# UKU207xx_power_board.net
KiCad netlist of a schematic drawn in Altium Designer
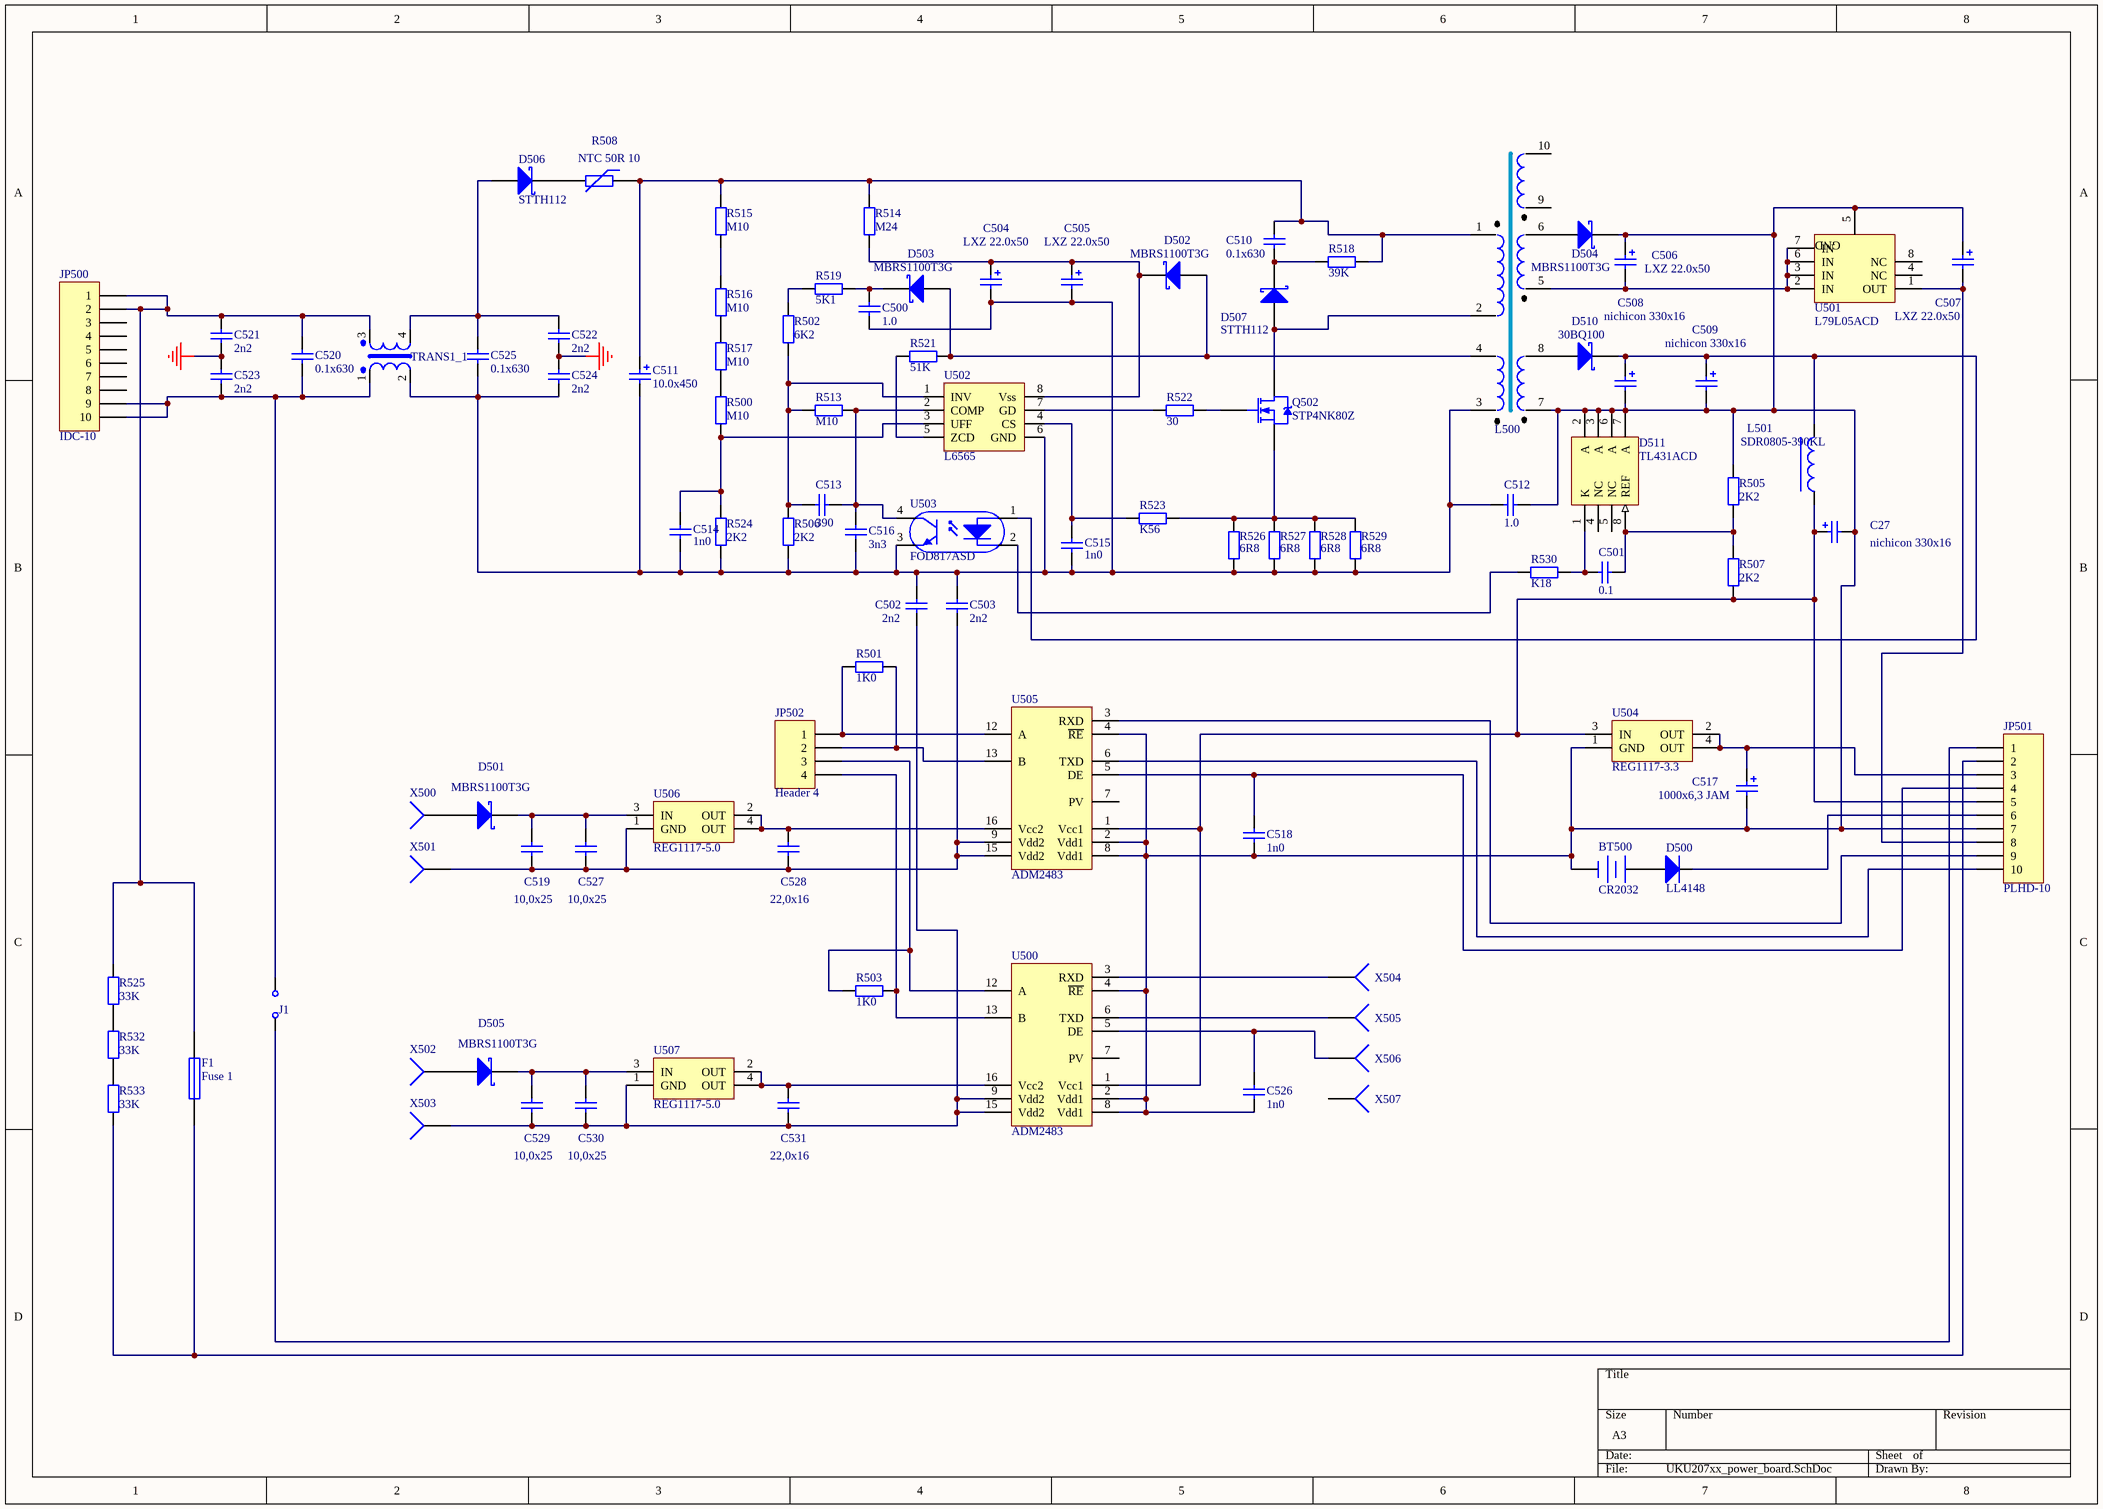
[diagram p0: UKU207xx_power_board.SchDoc]

(export (version "E")
  (design (tool "Eeschema 10.0.6"))
  (components
    (comp (ref "BT500")
      (value "CR2032")
      (footprint "BAT_HOLD_SMD1")
      (description "Multicell Battery")
      (fields (field (name "MANUFACTURER") "Generic Components") (field (name "PUBLISHER") "Altium Limited"))
      (libsource (lib "Miscellaneous Devices") (part "Battery"))
    )
    (comp (ref "C27")
      (value "nichicon 330x16")
      (footprint "el3")
      (description "Polarized Capacitor (Radial)")
      (fields (field (name "MANUFACTURER") "Generic Components") (field (name "PUBLISHER") "Altium Limited"))
      (libsource (lib "PAL") (part "Cap Pol1"))
    )
    (comp (ref "C500")
      (value "1.0")
      (footprint "_1206")
      (description "Capacitor (Semiconductor SIM Model)")
      (fields (field (name "MANUFACTURER") "Generic Components") (field (name "PUBLISHER") "Altium Limited"))
      (libsource (lib "Miscellaneous Devices") (part "Cap Semi"))
    )
    (comp (ref "C501")
      (value "0.1")
      (footprint "_1206")
      (description "Capacitor (Semiconductor SIM Model)")
      (fields (field (name "MANUFACTURER") "Generic Components") (field (name "PUBLISHER") "Altium Limited"))
      (libsource (lib "Miscellaneous Devices") (part "Cap Semi"))
    )
    (comp (ref "C502")
      (value "2n2")
      (footprint "C8")
      (description "Capacitor (Semiconductor SIM Model)")
      (fields (field (name "MANUFACTURER") "Generic Components") (field (name "PUBLISHER") "Altium Limited"))
      (libsource (lib "Miscellaneous Devices") (part "Cap Semi"))
    )
    (comp (ref "C503")
      (value "2n2")
      (footprint "C8")
      (description "Capacitor (Semiconductor SIM Model)")
      (fields (field (name "MANUFACTURER") "Generic Components") (field (name "PUBLISHER") "Altium Limited"))
      (libsource (lib "Miscellaneous Devices") (part "Cap Semi"))
    )
    (comp (ref "C504")
      (value "LXZ 22.0x50")
      (footprint "el3")
      (description "Polarized Capacitor (Radial)")
      (fields (field (name "MANUFACTURER") "Generic Components") (field (name "PUBLISHER") "Altium Limited"))
      (libsource (lib "PAL") (part "Cap Pol1"))
    )
    (comp (ref "C505")
      (value "LXZ 22.0x50")
      (footprint "el3")
      (description "Polarized Capacitor (Radial)")
      (fields (field (name "MANUFACTURER") "Generic Components") (field (name "PUBLISHER") "Altium Limited"))
      (libsource (lib "PAL") (part "Cap Pol1"))
    )
    (comp (ref "C506")
      (value "LXZ 22.0x50")
      (footprint "el3")
      (description "Polarized Capacitor (Radial)")
      (fields (field (name "MANUFACTURER") "Generic Components") (field (name "PUBLISHER") "Altium Limited"))
      (libsource (lib "PAL") (part "Cap Pol1"))
    )
    (comp (ref "C507")
      (value "LXZ 22.0x50")
      (footprint "el3")
      (description "Polarized Capacitor (Radial)")
      (fields (field (name "MANUFACTURER") "Generic Components") (field (name "PUBLISHER") "Altium Limited"))
      (libsource (lib "PAL") (part "Cap Pol1"))
    )
    (comp (ref "C508")
      (value "nichicon 330x16")
      (footprint "el3")
      (description "Polarized Capacitor (Radial)")
      (fields (field (name "MANUFACTURER") "Generic Components") (field (name "PUBLISHER") "Altium Limited"))
      (libsource (lib "PAL") (part "Cap Pol1"))
    )
    (comp (ref "C509")
      (value "nichicon 330x16")
      (footprint "el3")
      (description "Polarized Capacitor (Radial)")
      (fields (field (name "MANUFACTURER") "Generic Components") (field (name "PUBLISHER") "Altium Limited"))
      (libsource (lib "PAL") (part "Cap Pol1"))
    )
    (comp (ref "C510")
      (value "0.1x630")
      (footprint "c15")
      (description "Capacitor (Semiconductor SIM Model)")
      (fields (field (name "MANUFACTURER") "Generic Components") (field (name "PUBLISHER") "Altium Limited"))
      (libsource (lib "Miscellaneous Devices") (part "Cap Semi"))
    )
    (comp (ref "C511")
      (value "10.0x450")
      (footprint "el_15_25_h")
      (description "Polarized Capacitor (Radial)")
      (fields (field (name "MANUFACTURER") "Generic Components") (field (name "PUBLISHER") "Altium Limited"))
      (libsource (lib "PAL") (part "Cap Pol1"))
    )
    (comp (ref "C512")
      (value "1.0")
      (footprint "C8")
      (description "Capacitor (Semiconductor SIM Model)")
      (fields (field (name "MANUFACTURER") "Generic Components") (field (name "PUBLISHER") "Altium Limited"))
      (libsource (lib "Miscellaneous Devices") (part "Cap Semi"))
    )
    (comp (ref "C513")
      (value "390")
      (footprint "_1206")
      (description "Capacitor (Semiconductor SIM Model)")
      (fields (field (name "MANUFACTURER") "Generic Components") (field (name "PUBLISHER") "Altium Limited"))
      (libsource (lib "Miscellaneous Devices") (part "Cap Semi"))
    )
    (comp (ref "C514")
      (value "1n0")
      (footprint "_1206")
      (description "Capacitor (Semiconductor SIM Model)")
      (fields (field (name "MANUFACTURER") "Generic Components") (field (name "PUBLISHER") "Altium Limited"))
      (libsource (lib "Miscellaneous Devices") (part "Cap Semi"))
    )
    (comp (ref "C515")
      (value "1n0")
      (footprint "_1206")
      (description "Capacitor (Semiconductor SIM Model)")
      (fields (field (name "MANUFACTURER") "Generic Components") (field (name "PUBLISHER") "Altium Limited"))
      (libsource (lib "Miscellaneous Devices") (part "Cap Semi"))
    )
    (comp (ref "C516")
      (value "3n3")
      (footprint "_1206")
      (description "Capacitor (Semiconductor SIM Model)")
      (fields (field (name "MANUFACTURER") "Generic Components") (field (name "PUBLISHER") "Altium Limited"))
      (libsource (lib "Miscellaneous Devices") (part "Cap Semi"))
    )
    (comp (ref "C517")
      (value "1000x6,3 JAM")
      (footprint "el5")
      (description "Polarized Capacitor (Radial)")
      (fields (field (name "MANUFACTURER") "Generic Components") (field (name "PUBLISHER") "Altium Limited"))
      (libsource (lib "PAL") (part "Cap Pol1"))
    )
    (comp (ref "C518")
      (value "1n0")
      (footprint "_1206")
      (description "Capacitor (Semiconductor SIM Model)")
      (fields (field (name "MANUFACTURER") "Generic Components") (field (name "PUBLISHER") "Altium Limited"))
      (libsource (lib "Miscellaneous Devices") (part "Cap Semi"))
    )
    (comp (ref "C519")
      (value "1.0")
      (footprint "_1206")
      (description "Capacitor (Semiconductor SIM Model)")
      (fields
        (field (name "MANUFACTURER") "Generic Components")
        (field (name "ALTIUM_VALUE") "10,0x25")
        (field (name "PUBLISHER") "Altium Limited")
      )
      (libsource (lib "Miscellaneous Devices") (part "Cap Semi"))
    )
    (comp (ref "C520")
      (value "0.1x630")
      (footprint "c15")
      (description "Capacitor (Semiconductor SIM Model)")
      (fields (field (name "MANUFACTURER") "Generic Components") (field (name "PUBLISHER") "Altium Limited"))
      (libsource (lib "Miscellaneous Devices") (part "Cap Semi"))
    )
    (comp (ref "C521")
      (value "2n2")
      (footprint "C8")
      (description "Capacitor (Semiconductor SIM Model)")
      (fields (field (name "MANUFACTURER") "Generic Components") (field (name "PUBLISHER") "Altium Limited"))
      (libsource (lib "Miscellaneous Devices") (part "Cap Semi"))
    )
    (comp (ref "C522")
      (value "2n2")
      (footprint "c8")
      (description "Capacitor (Semiconductor SIM Model)")
      (fields (field (name "MANUFACTURER") "Generic Components") (field (name "PUBLISHER") "Altium Limited"))
      (libsource (lib "Miscellaneous Devices") (part "Cap Semi"))
    )
    (comp (ref "C523")
      (value "2n2")
      (footprint "c8")
      (description "Capacitor (Semiconductor SIM Model)")
      (fields (field (name "MANUFACTURER") "Generic Components") (field (name "PUBLISHER") "Altium Limited"))
      (libsource (lib "Miscellaneous Devices") (part "Cap Semi"))
    )
    (comp (ref "C524")
      (value "2n2")
      (footprint "c8")
      (description "Capacitor (Semiconductor SIM Model)")
      (fields (field (name "MANUFACTURER") "Generic Components") (field (name "PUBLISHER") "Altium Limited"))
      (libsource (lib "Miscellaneous Devices") (part "Cap Semi"))
    )
    (comp (ref "C525")
      (value "0.1х630")
      (footprint "c15")
      (description "Capacitor (Semiconductor SIM Model)")
      (fields (field (name "MANUFACTURER") "Generic Components") (field (name "PUBLISHER") "Altium Limited"))
      (libsource (lib "Miscellaneous Devices") (part "Cap Semi"))
    )
    (comp (ref "C526")
      (value "1n0")
      (footprint "_1206")
      (description "Capacitor (Semiconductor SIM Model)")
      (fields (field (name "MANUFACTURER") "Generic Components") (field (name "PUBLISHER") "Altium Limited"))
      (libsource (lib "Miscellaneous Devices") (part "Cap Semi"))
    )
    (comp (ref "C527")
      (value "1.0")
      (footprint "_1206")
      (description "Capacitor (Semiconductor SIM Model)")
      (fields
        (field (name "MANUFACTURER") "Generic Components")
        (field (name "ALTIUM_VALUE") "10,0x25")
        (field (name "PUBLISHER") "Altium Limited")
      )
      (libsource (lib "Miscellaneous Devices") (part "Cap Semi"))
    )
    (comp (ref "C528")
      (value "1.0")
      (footprint "_1206")
      (description "Capacitor (Semiconductor SIM Model)")
      (fields
        (field (name "MANUFACTURER") "Generic Components")
        (field (name "ALTIUM_VALUE") "22,0x16")
        (field (name "PUBLISHER") "Altium Limited")
      )
      (libsource (lib "Miscellaneous Devices") (part "Cap Semi"))
    )
    (comp (ref "C529")
      (value "1.0")
      (footprint "_1206")
      (description "Capacitor (Semiconductor SIM Model)")
      (fields
        (field (name "MANUFACTURER") "Generic Components")
        (field (name "ALTIUM_VALUE") "10,0x25")
        (field (name "PUBLISHER") "Altium Limited")
      )
      (libsource (lib "Miscellaneous Devices") (part "Cap Semi"))
    )
    (comp (ref "C530")
      (value "1.0")
      (footprint "_1206")
      (description "Capacitor (Semiconductor SIM Model)")
      (fields
        (field (name "MANUFACTURER") "Generic Components")
        (field (name "ALTIUM_VALUE") "10,0x25")
        (field (name "PUBLISHER") "Altium Limited")
      )
      (libsource (lib "Miscellaneous Devices") (part "Cap Semi"))
    )
    (comp (ref "C531")
      (value "1.0")
      (footprint "_1206")
      (description "Capacitor (Semiconductor SIM Model)")
      (fields
        (field (name "MANUFACTURER") "Generic Components")
        (field (name "ALTIUM_VALUE") "22,0x16")
        (field (name "PUBLISHER") "Altium Limited")
      )
      (libsource (lib "Miscellaneous Devices") (part "Cap Semi"))
    )
    (comp (ref "D500")
      (value "LL4148")
      (footprint "_1206d")
      (description "Default Diode")
      (fields (field (name "MANUFACTURER") "Generic Components") (field (name "PUBLISHER") "Altium Limited"))
      (libsource (lib "PAL") (part "Diode"))
    )
    (comp (ref "D501")
      (value "MBRS1100T3G")
      (footprint "D_6_3")
      (description "Schottky Rectifier")
      (fields
        (field (name "MANUFACTURER") "International Rectifier")
        (field (name "PUBLISHER") "Altium Limited")
      )
      (libsource (lib "IR Discrete Diode") (part "10BQ015"))
    )
    (comp (ref "D502")
      (value "MBRS1100T3G")
      (footprint "D_6_3")
      (description "Schottky Rectifier")
      (fields
        (field (name "MANUFACTURER") "International Rectifier")
        (field (name "PUBLISHER") "Altium Limited")
      )
      (libsource (lib "IR Discrete Diode") (part "10BQ015"))
    )
    (comp (ref "D503")
      (value "MBRS1100T3G")
      (footprint "D_6_3")
      (description "Schottky Rectifier")
      (fields
        (field (name "MANUFACTURER") "International Rectifier")
        (field (name "PUBLISHER") "Altium Limited")
      )
      (libsource (lib "IR Discrete Diode") (part "10BQ015"))
    )
    (comp (ref "D504")
      (value "MBRS1100T3G")
      (footprint "D_6_3")
      (description "Schottky Rectifier")
      (fields
        (field (name "MANUFACTURER") "International Rectifier")
        (field (name "PUBLISHER") "Altium Limited")
      )
      (libsource (lib "IR Discrete Diode") (part "10BQ015"))
    )
    (comp (ref "D505")
      (value "MBRS1100T3G")
      (footprint "D_6_3")
      (description "Schottky Rectifier")
      (fields
        (field (name "MANUFACTURER") "International Rectifier")
        (field (name "PUBLISHER") "Altium Limited")
      )
      (libsource (lib "IR Discrete Diode") (part "10BQ015"))
    )
    (comp (ref "D506")
      (value "STTH112")
      (footprint "D_6_3")
      (description "Schottky Diode")
      (fields
        (field (name "MANUFACTURER") "International Rectifier")
        (field (name "PUBLISHER") "Altium Limited")
      )
      (libsource (lib "IR Discrete Diode") (part "10BQ015"))
    )
    (comp (ref "D507")
      (value "STTH112")
      (footprint "D_6_3")
      (description "Schottky Diode")
      (fields
        (field (name "MANUFACTURER") "International Rectifier")
        (field (name "PUBLISHER") "Altium Limited")
      )
      (libsource (lib "IR Discrete Diode") (part "10BQ015"))
    )
    (comp (ref "D510")
      (value "30BQ100")
      (footprint "30BQ100")
      (description "Schottky Rectifier")
      (fields
        (field (name "MANUFACTURER") "International Rectifier")
        (field (name "PUBLISHER") "Altium Limited")
      )
      (libsource (lib "IR Discrete Diode") (part "10BQ015"))
    )
    (comp (ref "D511")
      (value "TL431ACD")
      (footprint "SO-G8")
      (description "Programmable Precision Reference")
      (fields (field (name "MANUFACTURER") "Motorola") (field (name "PUBLISHER") "Altium Limited"))
      (libsource (lib "Motorola Power Management Voltage Reference") (part "TL431ACD"))
    )
    (comp (ref "F1")
      (value "Fuse 1")
      (footprint "PIN-W2/E2.8")
      (description "Fuse")
      (fields (field (name "MANUFACTURER") "Generic Components") (field (name "PUBLISHER") "Altium Limited"))
      (libsource (lib "Miscellaneous Devices") (part "Fuse 1"))
    )
    (comp (ref "J1")
      (value "~")
      (footprint "BT5-2")
      (description "Switch")
      (fields (field (name "MANUFACTURER") "Generic Components") (field (name "PUBLISHER") "Altium Limited"))
      (libsource (lib "PAL") (part "JMP"))
    )
    (comp (ref "JP500")
      (value "IDC-10")
      (footprint "HDR2X5")
      (description "Header, 10-Pin")
      (fields (field (name "MANUFACTURER") "Generic Components") (field (name "PUBLISHER") "Altium Limited"))
      (libsource (lib "") (part "Header 10_1"))
    )
    (comp (ref "JP501")
      (value "PLHD-10")
      (footprint "HDR2X5")
      (description "Header, 10-Pin")
      (fields (field (name "MANUFACTURER") "Generic Components") (field (name "PUBLISHER") "Altium Limited"))
      (libsource (lib "Miscellaneous Connectors") (part "Header 10"))
    )
    (comp (ref "JP502")
      (value "Header 4")
      (footprint "PAL:2EDG-5.08-4")
      (description "Header, 4-Pin")
      (fields (field (name "MANUFACTURER") "Generic Components") (field (name "PUBLISHER") "Altium Limited"))
      (libsource (lib "Miscellaneous Connectors") (part "Header 4"))
    )
    (comp (ref "L500")
      (value "L220-K10")
      (footprint "trans_ring1")
      (description "Дроссель")
      (libsource (lib "PAL") (part "L1_dc_2"))
    )
    (comp (ref "L501")
      (value "SDR0805-390KL")
      (footprint "L10x10")
      (description "Magnetic-Core Inductor")
      (fields (field (name "MANUFACTURER") "Generic Components") (field (name "PUBLISHER") "Altium Limited"))
      (libsource (lib "PAL") (part "Inductor Konstr 2"))
    )
    (comp (ref "Q502")
      (value "STP4NK80Z")
      (footprint "TO220_h")
      (description "N-Channel Power MOSFET")
      (fields (field (name "MANUFACTURER") "Generic Components") (field (name "PUBLISHER") "Altium Limited"))
      (libsource (lib "Miscellaneous Devices") (part "NMOS-2"))
    )
    (comp (ref "R500")
      (value "M10")
      (footprint "_1206")
      (description "Resistor")
      (fields (field (name "MANUFACTURER") "Generic Components") (field (name "PUBLISHER") "Altium Limited"))
      (libsource (lib "") (part "Res2_1"))
    )
    (comp (ref "R501")
      (value "1K0")
      (footprint "_1206")
      (description "Resistor")
      (fields (field (name "MANUFACTURER") "Generic Components") (field (name "PUBLISHER") "Altium Limited"))
      (libsource (lib "") (part "Res2_2"))
    )
    (comp (ref "R502")
      (value "6K2")
      (footprint "_1206")
      (description "Resistor")
      (fields (field (name "MANUFACTURER") "Generic Components") (field (name "PUBLISHER") "Altium Limited"))
      (libsource (lib "") (part "Res2_1"))
    )
    (comp (ref "R503")
      (value "1K0")
      (footprint "_1206")
      (description "Resistor")
      (fields (field (name "MANUFACTURER") "Generic Components") (field (name "PUBLISHER") "Altium Limited"))
      (libsource (lib "") (part "Res2_2"))
    )
    (comp (ref "R505")
      (value "2K2")
      (footprint "_1206")
      (description "Resistor")
      (fields (field (name "MANUFACTURER") "Generic Components") (field (name "PUBLISHER") "Altium Limited"))
      (libsource (lib "") (part "Res2_1"))
    )
    (comp (ref "R506")
      (value "2K2")
      (footprint "_1206")
      (description "Resistor")
      (fields (field (name "MANUFACTURER") "Generic Components") (field (name "PUBLISHER") "Altium Limited"))
      (libsource (lib "") (part "Res2_1"))
    )
    (comp (ref "R507")
      (value "2K2")
      (footprint "_1206")
      (description "Resistor")
      (fields (field (name "MANUFACTURER") "Generic Components") (field (name "PUBLISHER") "Altium Limited"))
      (libsource (lib "") (part "Res2_1"))
    )
    (comp (ref "R508")
      (value "NTC 50R 10")
      (footprint "JVR07N")
      (description "Varistor (Voltage-Sensitive Resistor)")
      (fields (field (name "MANUFACTURER") "Generic Components") (field (name "PUBLISHER") "Altium Limited"))
      (libsource (lib "Miscellaneous Devices") (part "Res Varistor"))
    )
    (comp (ref "R513")
      (value "M10")
      (footprint "_1206")
      (description "Resistor")
      (fields (field (name "MANUFACTURER") "Generic Components") (field (name "PUBLISHER") "Altium Limited"))
      (libsource (lib "") (part "Res2_2"))
    )
    (comp (ref "R514")
      (value "M24")
      (footprint "AXIAL-0.7")
      (description "Resistor")
      (fields (field (name "MANUFACTURER") "Generic Components") (field (name "PUBLISHER") "Altium Limited"))
      (libsource (lib "") (part "Res2_1"))
    )
    (comp (ref "R515")
      (value "M10")
      (footprint "_1206")
      (description "Resistor")
      (fields (field (name "MANUFACTURER") "Generic Components") (field (name "PUBLISHER") "Altium Limited"))
      (libsource (lib "") (part "Res2_1"))
    )
    (comp (ref "R516")
      (value "M10")
      (footprint "_1206")
      (description "Resistor")
      (fields (field (name "MANUFACTURER") "Generic Components") (field (name "PUBLISHER") "Altium Limited"))
      (libsource (lib "") (part "Res2_1"))
    )
    (comp (ref "R517")
      (value "M10")
      (footprint "_1206")
      (description "Resistor")
      (fields (field (name "MANUFACTURER") "Generic Components") (field (name "PUBLISHER") "Altium Limited"))
      (libsource (lib "") (part "Res2_1"))
    )
    (comp (ref "R518")
      (value "39K")
      (footprint "AXIAL-0.7")
      (description "Resistor")
      (fields (field (name "MANUFACTURER") "Generic Components") (field (name "PUBLISHER") "Altium Limited"))
      (libsource (lib "") (part "Res2_2"))
    )
    (comp (ref "R519")
      (value "5K1")
      (footprint "_1206")
      (description "Resistor")
      (fields (field (name "MANUFACTURER") "Generic Components") (field (name "PUBLISHER") "Altium Limited"))
      (libsource (lib "") (part "Res2_2"))
    )
    (comp (ref "R521")
      (value "51K")
      (footprint "_1206")
      (description "Resistor")
      (fields (field (name "MANUFACTURER") "Generic Components") (field (name "PUBLISHER") "Altium Limited"))
      (libsource (lib "") (part "Res2_2"))
    )
    (comp (ref "R522")
      (value "30")
      (footprint "_1206")
      (description "Resistor")
      (fields (field (name "MANUFACTURER") "Generic Components") (field (name "PUBLISHER") "Altium Limited"))
      (libsource (lib "") (part "Res2_2"))
    )
    (comp (ref "R523")
      (value "K56")
      (footprint "_1206")
      (description "Resistor")
      (fields (field (name "MANUFACTURER") "Generic Components") (field (name "PUBLISHER") "Altium Limited"))
      (libsource (lib "") (part "Res2_2"))
    )
    (comp (ref "R524")
      (value "2K2")
      (footprint "_1206")
      (description "Resistor")
      (fields (field (name "MANUFACTURER") "Generic Components") (field (name "PUBLISHER") "Altium Limited"))
      (libsource (lib "") (part "Res2_1"))
    )
    (comp (ref "R525")
      (value "33K")
      (footprint "_1206")
      (description "Resistor")
      (fields (field (name "MANUFACTURER") "Generic Components") (field (name "PUBLISHER") "Altium Limited"))
      (libsource (lib "") (part "Res2_1"))
    )
    (comp (ref "R526")
      (value "6R8")
      (footprint "_1206")
      (description "Resistor")
      (fields (field (name "MANUFACTURER") "Generic Components") (field (name "PUBLISHER") "Altium Limited"))
      (libsource (lib "Miscellaneous Devices") (part "Res2"))
    )
    (comp (ref "R527")
      (value "6R8")
      (footprint "_1206")
      (description "Resistor")
      (fields (field (name "MANUFACTURER") "Generic Components") (field (name "PUBLISHER") "Altium Limited"))
      (libsource (lib "Miscellaneous Devices") (part "Res2"))
    )
    (comp (ref "R528")
      (value "6R8")
      (footprint "_1206")
      (description "Resistor")
      (fields (field (name "MANUFACTURER") "Generic Components") (field (name "PUBLISHER") "Altium Limited"))
      (libsource (lib "Miscellaneous Devices") (part "Res2"))
    )
    (comp (ref "R529")
      (value "6R8")
      (footprint "_1206")
      (description "Resistor")
      (fields (field (name "MANUFACTURER") "Generic Components") (field (name "PUBLISHER") "Altium Limited"))
      (libsource (lib "Miscellaneous Devices") (part "Res2"))
    )
    (comp (ref "R530")
      (value "K18")
      (footprint "_1206")
      (description "Resistor")
      (fields (field (name "MANUFACTURER") "Generic Components") (field (name "PUBLISHER") "Altium Limited"))
      (libsource (lib "") (part "Res2_2"))
    )
    (comp (ref "R532")
      (value "33K")
      (footprint "_1206")
      (description "Resistor")
      (fields (field (name "MANUFACTURER") "Generic Components") (field (name "PUBLISHER") "Altium Limited"))
      (libsource (lib "") (part "Res2_1"))
    )
    (comp (ref "R533")
      (value "33K")
      (footprint "_1206")
      (description "Resistor")
      (fields (field (name "MANUFACTURER") "Generic Components") (field (name "PUBLISHER") "Altium Limited"))
      (libsource (lib "") (part "Res2_1"))
    )
    (comp (ref "T500")
      (value "TRANS1_1")
      (footprint "3030R4")
      (fields (field (name "MANUFACTURER") "Generic Components") (field (name "PUBLISHER") "Altium Limited"))
      (libsource (lib "PAL") (part "TRANS1_1"))
    )
    (comp (ref "U500") (value "ADM2483") (footprint "SO-G16/D10.4") (libsource (lib "PAL") (part "ADM2483")))
    (comp (ref "U501")
      (value "L79L05ACD")
      (footprint "SO-G8")
      (description "Negative Voltage Regulator")
      (fields (field (name "MANUFACTURER") "ST-Microelectronics") (field (name "PUBLISHER") "Altium Limited"))
      (libsource (lib "ST Power Mgt Voltage Regulator") (part "L79L05ACD"))
    )
    (comp (ref "U502") (value "L6565") (footprint "so-g8") (libsource (lib "PAL") (part "L6565")))
    (comp (ref "U503") (value "FOD817ASD") (footprint "FOD817ASD") (libsource (lib "PAL") (part "F00817ASD")))
    (comp (ref "U504")
      (value "REG1117-3.3")
      (footprint "DSO-G3")
      (description "800mA and 1A Low Dropout Positive Regulator 2.85V, 3.3V, 5V, and Adjustable")
      (fields (field (name "MANUFACTURER") "Burr-Brown") (field (name "PUBLISHER") "Altium Limited"))
      (libsource (lib "BB Power Mgt Voltage Regulator") (part "REG1117-3.3"))
    )
    (comp (ref "U505") (value "ADM2483") (footprint "SO-G16/D10.4") (libsource (lib "PAL") (part "ADM2483")))
    (comp (ref "U506")
      (value "REG1117-5.0")
      (footprint "DSO-G3")
      (description "800mA and 1A Low Dropout Positive Regulator 2.85V, 3.3V, 5V, and Adjustable")
      (fields (field (name "MANUFACTURER") "Burr-Brown") (field (name "PUBLISHER") "Altium Limited"))
      (libsource (lib "BB Power Mgt Voltage Regulator") (part "REG1117-3.3"))
    )
    (comp (ref "U507")
      (value "REG1117-5.0")
      (footprint "DSO-G3")
      (description "800mA and 1A Low Dropout Positive Regulator 2.85V, 3.3V, 5V, and Adjustable")
      (fields (field (name "MANUFACTURER") "Burr-Brown") (field (name "PUBLISHER") "Altium Limited"))
      (libsource (lib "BB Power Mgt Voltage Regulator") (part "REG1117-3.3"))
    )
    (comp (ref "X500")
      (value "Socket")
      (footprint "PIN1")
      (fields (field (name "MANUFACTURER") "Generic Components") (field (name "PUBLISHER") "Altium Limited"))
      (libsource (lib "Miscellaneous Connectors") (part "Socket"))
    )
    (comp (ref "X501")
      (value "Socket")
      (footprint "PIN1")
      (fields (field (name "MANUFACTURER") "Generic Components") (field (name "PUBLISHER") "Altium Limited"))
      (libsource (lib "Miscellaneous Connectors") (part "Socket"))
    )
    (comp (ref "X502")
      (value "Socket")
      (footprint "PIN1")
      (fields (field (name "MANUFACTURER") "Generic Components") (field (name "PUBLISHER") "Altium Limited"))
      (libsource (lib "Miscellaneous Connectors") (part "Socket"))
    )
    (comp (ref "X503")
      (value "Socket")
      (footprint "PIN1")
      (fields (field (name "MANUFACTURER") "Generic Components") (field (name "PUBLISHER") "Altium Limited"))
      (libsource (lib "Miscellaneous Connectors") (part "Socket"))
    )
    (comp (ref "X504")
      (value "Socket")
      (footprint "PIN1")
      (fields (field (name "MANUFACTURER") "Generic Components") (field (name "PUBLISHER") "Altium Limited"))
      (libsource (lib "Miscellaneous Connectors") (part "Socket"))
    )
    (comp (ref "X505")
      (value "Socket")
      (footprint "PIN1")
      (fields (field (name "MANUFACTURER") "Generic Components") (field (name "PUBLISHER") "Altium Limited"))
      (libsource (lib "Miscellaneous Connectors") (part "Socket"))
    )
    (comp (ref "X506")
      (value "Socket")
      (footprint "PIN1")
      (fields (field (name "MANUFACTURER") "Generic Components") (field (name "PUBLISHER") "Altium Limited"))
      (libsource (lib "Miscellaneous Connectors") (part "Socket"))
    )
    (comp (ref "X507")
      (value "Socket")
      (footprint "PIN1")
      (fields (field (name "MANUFACTURER") "Generic Components") (field (name "PUBLISHER") "Altium Limited"))
      (libsource (lib "Miscellaneous Connectors") (part "Socket"))
    )
  )
  (nets
    (net (code "1") (name "GND_GND") (class "Default")
      (node (ref "C521") (pin "1") (pinfunction "1_1") (pintype "passive"))
      (node (ref "C522") (pin "1") (pinfunction "1_1") (pintype "passive"))
      (node (ref "C523") (pin "2") (pinfunction "2_2") (pintype "passive"))
      (node (ref "C524") (pin "2") (pinfunction "2_2") (pintype "passive"))
    )
    (net (code "2") (name "Net-(BT500-+)") (class "Default")
      (node (ref "BT500") (pin "1") (pinfunction "+_1") (pintype "passive"))
      (node (ref "D500") (pin "1") (pinfunction "A_1") (pintype "passive"))
    )
    (net (code "3") (name "Net-(BT500--)") (class "Default")
      (node (ref "BT500") (pin "2") (pinfunction "-_2") (pintype "passive"))
      (node (ref "C27") (pin "2") (pinfunction "2_2") (pintype "passive"))
      (node (ref "C506") (pin "1") (pinfunction "1_1") (pintype "passive"))
      (node (ref "C507") (pin "1") (pinfunction "1_1") (pintype "passive"))
      (node (ref "C508") (pin "2") (pinfunction "2_2") (pintype "passive"))
      (node (ref "C509") (pin "2") (pinfunction "2_2") (pintype "passive"))
      (node (ref "C512") (pin "1") (pinfunction "1_1") (pintype "passive"))
      (node (ref "C517") (pin "2") (pinfunction "2_2") (pintype "passive"))
      (node (ref "C518") (pin "1") (pinfunction "1_1") (pintype "passive"))
      (node (ref "C526") (pin "1") (pinfunction "1_1") (pintype "passive"))
      (node (ref "D504") (pin "2") (pinfunction "K_2") (pintype "passive"))
      (node (ref "D511") (pin "2") (pinfunction "A_2") (pintype "passive"))
      (node (ref "D511") (pin "3") (pinfunction "A_3") (pintype "passive"))
      (node (ref "D511") (pin "6") (pinfunction "A_6") (pintype "passive"))
      (node (ref "D511") (pin "7") (pinfunction "A_7") (pintype "passive"))
      (node (ref "JP501") (pin "7") (pinfunction "7_7") (pintype "passive"))
      (node (ref "L500") (pin "7") (pintype "passive"))
      (node (ref "R505") (pin "2") (pinfunction "2_2") (pintype "passive"))
      (node (ref "U500") (pin "2") (pinfunction "Vdd1_2") (pintype "passive"))
      (node (ref "U500") (pin "4") (pinfunction "~{RE}_4") (pintype "passive"))
      (node (ref "U500") (pin "8") (pinfunction "Vdd1_8") (pintype "passive"))
      (node (ref "U501") (pin "5") (pinfunction "GND_5") (pintype "power_in"))
      (node (ref "U504") (pin "1") (pinfunction "GND_1") (pintype "power_in"))
      (node (ref "U505") (pin "2") (pinfunction "Vdd1_2") (pintype "passive"))
      (node (ref "U505") (pin "4") (pinfunction "~{RE}_4") (pintype "passive"))
      (node (ref "U505") (pin "8") (pinfunction "Vdd1_8") (pintype "passive"))
    )
    (net (code "4") (name "Net-(C506-Pad2)") (class "Default")
      (node (ref "C506") (pin "2") (pinfunction "2_2") (pintype "passive"))
      (node (ref "L500") (pin "5") (pintype "passive"))
      (node (ref "U501") (pin "2") (pinfunction "IN_2") (pintype "power_in"))
      (node (ref "U501") (pin "3") (pinfunction "IN_3") (pintype "power_in"))
      (node (ref "U501") (pin "6") (pinfunction "IN_6") (pintype "power_in"))
      (node (ref "U501") (pin "7") (pinfunction "IN_7") (pintype "power_in"))
    )
    (net (code "5") (name "Net-(C510-Pad2)") (class "Default")
      (node (ref "C510") (pin "2") (pinfunction "2_2") (pintype "passive"))
      (node (ref "C511") (pin "1") (pinfunction "1_1") (pintype "passive"))
      (node (ref "L500") (pin "1") (pintype "passive"))
      (node (ref "R508") (pin "1") (pinfunction "1_1") (pintype "passive"))
      (node (ref "R514") (pin "2") (pinfunction "2_2") (pintype "passive"))
      (node (ref "R515") (pin "2") (pinfunction "2_2") (pintype "passive"))
      (node (ref "R518") (pin "1") (pinfunction "1_1") (pintype "passive"))
    )
    (net (code "6") (name "Net-(C517-Pad1)") (class "Default")
      (node (ref "C517") (pin "1") (pinfunction "1_1") (pintype "passive"))
      (node (ref "JP501") (pin "3") (pinfunction "3_3") (pintype "passive"))
      (node (ref "U504") (pin "2") (pinfunction "OUT_2") (pintype "power_in"))
      (node (ref "U504") (pin "4") (pinfunction "OUT_4") (pintype "power_in"))
    )
    (net (code "7") (name "Net-(D500-K)") (class "Default")
      (node (ref "D500") (pin "2") (pinfunction "K_2") (pintype "passive"))
      (node (ref "JP501") (pin "6") (pinfunction "6_6") (pintype "passive"))
    )
    (net (code "8") (name "Net-(D501-A)") (class "Default")
      (node (ref "D501") (pin "1") (pinfunction "A_1") (pintype "passive"))
      (node (ref "X500") (pin "1") (pinfunction "1_1") (pintype "passive"))
    )
    (net (code "9") (name "Net-(D501-K)") (class "Default")
      (node (ref "C519") (pin "2") (pinfunction "2_2") (pintype "passive"))
      (node (ref "C527") (pin "2") (pinfunction "2_2") (pintype "passive"))
      (node (ref "D501") (pin "2") (pinfunction "K_2") (pintype "passive"))
      (node (ref "U506") (pin "3") (pinfunction "IN_3") (pintype "power_in"))
    )
    (net (code "10") (name "Net-(D502-A)") (class "Default")
      (node (ref "D502") (pin "1") (pinfunction "A_1") (pintype "passive"))
      (node (ref "D503") (pin "1") (pinfunction "A_1") (pintype "passive"))
      (node (ref "L500") (pin "4") (pintype "passive"))
      (node (ref "R521") (pin "1") (pinfunction "1_1") (pintype "passive"))
    )
    (net (code "11") (name "Net-(D502-K)") (class "Default")
      (node (ref "C504") (pin "1") (pinfunction "1_1") (pintype "passive"))
      (node (ref "C505") (pin "1") (pinfunction "1_1") (pintype "passive"))
      (node (ref "D502") (pin "2") (pinfunction "K_2") (pintype "passive"))
      (node (ref "R514") (pin "1") (pinfunction "1_1") (pintype "passive"))
      (node (ref "U502") (pin "8") (pinfunction "Vss_8") (pintype "passive"))
    )
    (net (code "12") (name "Net-(D503-K)") (class "Default")
      (node (ref "C500") (pin "2") (pinfunction "2_2") (pintype "passive"))
      (node (ref "D503") (pin "2") (pinfunction "K_2") (pintype "passive"))
      (node (ref "R519") (pin "1") (pinfunction "1_1") (pintype "passive"))
    )
    (net (code "13") (name "Net-(D504-A)") (class "Default")
      (node (ref "D504") (pin "1") (pinfunction "A_1") (pintype "passive"))
      (node (ref "L500") (pin "6") (pintype "passive"))
    )
    (net (code "14") (name "Net-(D505-A)") (class "Default")
      (node (ref "D505") (pin "1") (pinfunction "A_1") (pintype "passive"))
      (node (ref "X502") (pin "1") (pinfunction "1_1") (pintype "passive"))
    )
    (net (code "15") (name "Net-(D505-K)") (class "Default")
      (node (ref "C529") (pin "2") (pinfunction "2_2") (pintype "passive"))
      (node (ref "C530") (pin "2") (pinfunction "2_2") (pintype "passive"))
      (node (ref "D505") (pin "2") (pinfunction "K_2") (pintype "passive"))
      (node (ref "U507") (pin "3") (pinfunction "IN_3") (pintype "power_in"))
    )
    (net (code "16") (name "Net-(D506-A)") (class "Default")
      (node (ref "C522") (pin "2") (pinfunction "2_2") (pintype "passive"))
      (node (ref "C525") (pin "2") (pinfunction "2_2") (pintype "passive"))
      (node (ref "D506") (pin "1") (pinfunction "A_1") (pintype "passive"))
      (node (ref "T500") (pin "4") (pinfunction "Sec1-_4") (pintype "passive"))
    )
    (net (code "17") (name "Net-(D506-K)") (class "Default")
      (node (ref "D506") (pin "2") (pinfunction "K_2") (pintype "passive"))
      (node (ref "R508") (pin "2") (pinfunction "2_2") (pintype "passive"))
    )
    (net (code "18") (name "Net-(D507-A)") (class "Default")
      (node (ref "D507") (pin "1") (pinfunction "A_1") (pintype "passive"))
      (node (ref "L500") (pin "2") (pintype "passive"))
      (node (ref "Q502") (pin "2") (pinfunction "D_2") (pintype "passive"))
    )
    (net (code "19") (name "Net-(D507-K)") (class "Default")
      (node (ref "C510") (pin "1") (pinfunction "1_1") (pintype "passive"))
      (node (ref "D507") (pin "2") (pinfunction "K_2") (pintype "passive"))
      (node (ref "R518") (pin "2") (pinfunction "2_2") (pintype "passive"))
    )
    (net (code "20") (name "Net-(D510-A)") (class "Default")
      (node (ref "D510") (pin "1") (pinfunction "A_1") (pintype "passive"))
      (node (ref "L500") (pin "8") (pintype "passive"))
    )
    (net (code "21") (name "Net-(D510-K)") (class "Default")
      (node (ref "C508") (pin "1") (pinfunction "1_1") (pintype "passive"))
      (node (ref "C509") (pin "1") (pinfunction "1_1") (pintype "passive"))
      (node (ref "D510") (pin "2") (pinfunction "K_2") (pintype "passive"))
      (node (ref "L501") (pin "2") (pinfunction "2_2") (pintype "passive"))
      (node (ref "U503") (pin "1") (pinfunction "0_1") (pintype "passive"))
    )
    (net (code "22") (name "Net-(D511-K)") (class "Default")
      (node (ref "C501") (pin "2") (pinfunction "2_2") (pintype "passive"))
      (node (ref "D511") (pin "1") (pinfunction "K_1") (pintype "passive"))
      (node (ref "R530") (pin "1") (pinfunction "1_1") (pintype "passive"))
    )
    (net (code "23") (name "Net-(D511-REF)") (class "Default")
      (node (ref "C501") (pin "1") (pinfunction "1_1") (pintype "passive"))
      (node (ref "D511") (pin "8") (pinfunction "REF_8") (pintype "input"))
      (node (ref "R505") (pin "1") (pinfunction "1_1") (pintype "passive"))
      (node (ref "R507") (pin "2") (pinfunction "2_2") (pintype "passive"))
    )
    (net (code "24") (name "Net-(F1-Pad1)") (class "Default")
      (node (ref "F1") (pin "1") (pinfunction "1_1") (pintype "passive"))
      (node (ref "JP501") (pin "2") (pinfunction "2_2") (pintype "passive"))
      (node (ref "R533") (pin "1") (pinfunction "1_1") (pintype "passive"))
    )
    (net (code "25") (name "Net-(J1-Pad2)") (class "Default")
      (node (ref "J1") (pin "2") (pinfunction "2_2") (pintype "passive"))
      (node (ref "JP501") (pin "1") (pinfunction "1_1") (pintype "passive"))
    )
    (net (code "26") (name "Net-(Q502-G)") (class "Default")
      (node (ref "Q502") (pin "1") (pinfunction "G_1") (pintype "passive"))
      (node (ref "R522") (pin "1") (pinfunction "1_1") (pintype "passive"))
    )
    (net (code "27") (name "Net-(Q502-S)") (class "Default")
      (node (ref "Q502") (pin "3") (pinfunction "S_3") (pintype "passive"))
      (node (ref "R523") (pin "1") (pinfunction "1_1") (pintype "passive"))
      (node (ref "R526") (pin "1") (pinfunction "1_1") (pintype "passive"))
      (node (ref "R527") (pin "1") (pinfunction "1_1") (pintype "passive"))
      (node (ref "R528") (pin "1") (pinfunction "1_1") (pintype "passive"))
      (node (ref "R529") (pin "1") (pinfunction "1_1") (pintype "passive"))
    )
    (net (code "28") (name "Net-(R500-Pad2)") (class "Default")
      (node (ref "R500") (pin "2") (pinfunction "2_2") (pintype "passive"))
      (node (ref "R517") (pin "1") (pinfunction "1_1") (pintype "passive"))
    )
    (net (code "29") (name "Net-(R502-Pad2)") (class "Default")
      (node (ref "R502") (pin "2") (pinfunction "2_2") (pintype "passive"))
      (node (ref "R519") (pin "2") (pinfunction "2_2") (pintype "passive"))
    )
    (net (code "30") (name "Net-(R515-Pad1)") (class "Default")
      (node (ref "R515") (pin "1") (pinfunction "1_1") (pintype "passive"))
      (node (ref "R516") (pin "2") (pinfunction "2_2") (pintype "passive"))
    )
    (net (code "31") (name "Net-(R516-Pad1)") (class "Default")
      (node (ref "R516") (pin "1") (pinfunction "1_1") (pintype "passive"))
      (node (ref "R517") (pin "2") (pinfunction "2_2") (pintype "passive"))
    )
    (net (code "32") (name "Net-(R525-Pad1)") (class "Default")
      (node (ref "R525") (pin "1") (pinfunction "1_1") (pintype "passive"))
      (node (ref "R532") (pin "2") (pinfunction "2_2") (pintype "passive"))
    )
    (net (code "33") (name "Net-(R532-Pad1)") (class "Default")
      (node (ref "R532") (pin "1") (pinfunction "1_1") (pintype "passive"))
      (node (ref "R533") (pin "2") (pinfunction "2_2") (pintype "passive"))
    )
    (net (code "34") (name "Net-(T500-Pri+)") (class "Default")
      (node (ref "C520") (pin "1") (pinfunction "1_1") (pintype "passive"))
      (node (ref "C523") (pin "1") (pinfunction "1_1") (pintype "passive"))
      (node (ref "J1") (pin "1") (pinfunction "1_1") (pintype "passive"))
      (node (ref "JP500") (pin "10") (pinfunction "10_10") (pintype "passive"))
      (node (ref "JP500") (pin "9") (pinfunction "9_9") (pintype "passive"))
      (node (ref "T500") (pin "1") (pinfunction "Pri+_1") (pintype "passive"))
    )
    (net (code "35") (name "Net-(T500-Pri-)") (class "Default")
      (node (ref "C500") (pin "1") (pinfunction "1_1") (pintype "passive"))
      (node (ref "C502") (pin "2") (pinfunction "2_2") (pintype "passive"))
      (node (ref "C503") (pin "2") (pinfunction "2_2") (pintype "passive"))
      (node (ref "C504") (pin "2") (pinfunction "2_2") (pintype "passive"))
      (node (ref "C505") (pin "2") (pinfunction "2_2") (pintype "passive"))
      (node (ref "C511") (pin "2") (pinfunction "2_2") (pintype "passive"))
      (node (ref "C512") (pin "2") (pinfunction "2_2") (pintype "passive"))
      (node (ref "C514") (pin "2") (pinfunction "2_2") (pintype "passive"))
      (node (ref "C515") (pin "2") (pinfunction "2_2") (pintype "passive"))
      (node (ref "C516") (pin "1") (pinfunction "1_1") (pintype "passive"))
      (node (ref "C524") (pin "1") (pinfunction "1_1") (pintype "passive"))
      (node (ref "C525") (pin "1") (pinfunction "1_1") (pintype "passive"))
      (node (ref "L500") (pin "3") (pintype "passive"))
      (node (ref "R506") (pin "1") (pinfunction "1_1") (pintype "passive"))
      (node (ref "R524") (pin "1") (pinfunction "1_1") (pintype "passive"))
      (node (ref "R526") (pin "2") (pinfunction "2_2") (pintype "passive"))
      (node (ref "R527") (pin "2") (pinfunction "2_2") (pintype "passive"))
      (node (ref "R528") (pin "2") (pinfunction "2_2") (pintype "passive"))
      (node (ref "R529") (pin "2") (pinfunction "2_2") (pintype "passive"))
      (node (ref "T500") (pin "2") (pinfunction "Pri-_2") (pintype "passive"))
      (node (ref "U502") (pin "6") (pinfunction "GND_6") (pintype "passive"))
      (node (ref "U503") (pin "3") (pinfunction "4_3") (pintype "passive"))
    )
    (net (code "36") (name "Net-(T500-Sec1+)") (class "Default")
      (node (ref "C520") (pin "2") (pinfunction "2_2") (pintype "passive"))
      (node (ref "C521") (pin "2") (pinfunction "2_2") (pintype "passive"))
      (node (ref "F1") (pin "2") (pinfunction "2_2") (pintype "passive"))
      (node (ref "JP500") (pin "1") (pinfunction "1_1") (pintype "passive"))
      (node (ref "JP500") (pin "2") (pinfunction "2_2") (pintype "passive"))
      (node (ref "R525") (pin "2") (pinfunction "2_2") (pintype "passive"))
      (node (ref "T500") (pin "3") (pinfunction "Sec1+_3") (pintype "passive"))
    )
    (net (code "37") (name "Net-(U500-A)") (class "Default")
      (node (ref "JP502") (pin "3") (pinfunction "3_3") (pintype "passive"))
      (node (ref "R503") (pin "2") (pinfunction "2_2") (pintype "passive"))
      (node (ref "U500") (pin "12") (pinfunction "A_12") (pintype "passive"))
    )
    (net (code "38") (name "Net-(U500-B)") (class "Default")
      (node (ref "JP502") (pin "4") (pinfunction "4_4") (pintype "passive"))
      (node (ref "R503") (pin "1") (pinfunction "1_1") (pintype "passive"))
      (node (ref "U500") (pin "13") (pinfunction "B_13") (pintype "passive"))
    )
    (net (code "39") (name "Net-(U500-DE)") (class "Default")
      (node (ref "C526") (pin "2") (pinfunction "2_2") (pintype "passive"))
      (node (ref "U500") (pin "5") (pinfunction "DE_5") (pintype "passive"))
      (node (ref "X506") (pin "1") (pinfunction "1_1") (pintype "passive"))
    )
    (net (code "40") (name "Net-(U500-RXD)") (class "Default")
      (node (ref "U500") (pin "3") (pinfunction "RXD_3") (pintype "passive"))
      (node (ref "X504") (pin "1") (pinfunction "1_1") (pintype "passive"))
    )
    (net (code "41") (name "Net-(U500-TXD)") (class "Default")
      (node (ref "U500") (pin "6") (pinfunction "TXD_6") (pintype "passive"))
      (node (ref "X505") (pin "1") (pinfunction "1_1") (pintype "passive"))
    )
    (net (code "42") (name "Net-(U500-Vcc1)") (class "Default")
      (node (ref "C27") (pin "1") (pinfunction "1_1") (pintype "passive"))
      (node (ref "JP501") (pin "5") (pinfunction "5_5") (pintype "passive"))
      (node (ref "L501") (pin "1") (pinfunction "1_1") (pintype "passive"))
      (node (ref "R507") (pin "1") (pinfunction "1_1") (pintype "passive"))
      (node (ref "U500") (pin "1") (pinfunction "Vcc1_1") (pintype "passive"))
      (node (ref "U504") (pin "3") (pinfunction "IN_3") (pintype "power_in"))
      (node (ref "U505") (pin "1") (pinfunction "Vcc1_1") (pintype "passive"))
    )
    (net (code "43") (name "Net-(U500-Vcc2)") (class "Default")
      (node (ref "C531") (pin "2") (pinfunction "2_2") (pintype "passive"))
      (node (ref "U500") (pin "16") (pinfunction "Vcc2_16") (pintype "passive"))
      (node (ref "U507") (pin "2") (pinfunction "OUT_2") (pintype "power_in"))
      (node (ref "U507") (pin "4") (pinfunction "OUT_4") (pintype "power_in"))
    )
    (net (code "44") (name "Net-(U501-OUT)") (class "Default")
      (node (ref "C507") (pin "2") (pinfunction "2_2") (pintype "passive"))
      (node (ref "JP501") (pin "8") (pinfunction "8_8") (pintype "passive"))
      (node (ref "U501") (pin "1") (pinfunction "OUT_1") (pintype "power_in"))
    )
    (net (code "45") (name "Net-(U502-COMP)") (class "Default")
      (node (ref "C513") (pin "2") (pinfunction "2_2") (pintype "passive"))
      (node (ref "C516") (pin "2") (pinfunction "2_2") (pintype "passive"))
      (node (ref "R513") (pin "1") (pinfunction "1_1") (pintype "passive"))
      (node (ref "U502") (pin "2") (pinfunction "COMP_2") (pintype "passive"))
      (node (ref "U503") (pin "4") (pinfunction "2_4") (pintype "passive"))
    )
    (net (code "46") (name "Net-(U502-CS)") (class "Default")
      (node (ref "C515") (pin "1") (pinfunction "1_1") (pintype "passive"))
      (node (ref "R523") (pin "2") (pinfunction "2_2") (pintype "passive"))
      (node (ref "U502") (pin "4") (pinfunction "CS_4") (pintype "passive"))
    )
    (net (code "47") (name "Net-(U502-GD)") (class "Default")
      (node (ref "R522") (pin "2") (pinfunction "2_2") (pintype "passive"))
      (node (ref "U502") (pin "7") (pinfunction "GD_7") (pintype "passive"))
    )
    (net (code "48") (name "Net-(U502-INV)") (class "Default")
      (node (ref "C513") (pin "1") (pinfunction "1_1") (pintype "passive"))
      (node (ref "R502") (pin "1") (pinfunction "1_1") (pintype "passive"))
      (node (ref "R506") (pin "2") (pinfunction "2_2") (pintype "passive"))
      (node (ref "R513") (pin "2") (pinfunction "2_2") (pintype "passive"))
      (node (ref "U502") (pin "1") (pinfunction "INV_1") (pintype "passive"))
    )
    (net (code "49") (name "Net-(U502-UFF)") (class "Default")
      (node (ref "C514") (pin "1") (pinfunction "1_1") (pintype "passive"))
      (node (ref "R500") (pin "1") (pinfunction "1_1") (pintype "passive"))
      (node (ref "R524") (pin "2") (pinfunction "2_2") (pintype "passive"))
      (node (ref "U502") (pin "3") (pinfunction "UFF_3") (pintype "passive"))
    )
    (net (code "50") (name "Net-(U502-ZCD)") (class "Default")
      (node (ref "R521") (pin "2") (pinfunction "2_2") (pintype "passive"))
      (node (ref "U502") (pin "5") (pinfunction "ZCD_5") (pintype "passive"))
    )
    (net (code "51") (name "Net-(U503-1)") (class "Default")
      (node (ref "R530") (pin "2") (pinfunction "2_2") (pintype "passive"))
      (node (ref "U503") (pin "2") (pinfunction "1_2") (pintype "passive"))
    )
    (net (code "52") (name "Net-(U505-A)") (class "Default")
      (node (ref "JP502") (pin "1") (pinfunction "1_1") (pintype "passive"))
      (node (ref "R501") (pin "2") (pinfunction "2_2") (pintype "passive"))
      (node (ref "U505") (pin "12") (pinfunction "A_12") (pintype "passive"))
    )
    (net (code "53") (name "Net-(U505-B)") (class "Default")
      (node (ref "JP502") (pin "2") (pinfunction "2_2") (pintype "passive"))
      (node (ref "R501") (pin "1") (pinfunction "1_1") (pintype "passive"))
      (node (ref "U505") (pin "13") (pinfunction "B_13") (pintype "passive"))
    )
    (net (code "54") (name "Net-(U505-DE)") (class "Default")
      (node (ref "C518") (pin "2") (pinfunction "2_2") (pintype "passive"))
      (node (ref "JP501") (pin "4") (pinfunction "4_4") (pintype "passive"))
      (node (ref "U505") (pin "5") (pinfunction "DE_5") (pintype "passive"))
    )
    (net (code "55") (name "Net-(U505-RXD)") (class "Default")
      (node (ref "JP501") (pin "9") (pinfunction "9_9") (pintype "passive"))
      (node (ref "U505") (pin "3") (pinfunction "RXD_3") (pintype "passive"))
    )
    (net (code "56") (name "Net-(U505-TXD)") (class "Default")
      (node (ref "JP501") (pin "10") (pinfunction "10_10") (pintype "passive"))
      (node (ref "U505") (pin "6") (pinfunction "TXD_6") (pintype "passive"))
    )
    (net (code "57") (name "Net-(U505-Vcc2)") (class "Default")
      (node (ref "C528") (pin "2") (pinfunction "2_2") (pintype "passive"))
      (node (ref "U505") (pin "16") (pinfunction "Vcc2_16") (pintype "passive"))
      (node (ref "U506") (pin "2") (pinfunction "OUT_2") (pintype "power_in"))
      (node (ref "U506") (pin "4") (pinfunction "OUT_4") (pintype "power_in"))
    )
    (net (code "58") (name "Net-(U506-GND)") (class "Default")
      (node (ref "C503") (pin "1") (pinfunction "1_1") (pintype "passive"))
      (node (ref "C519") (pin "1") (pinfunction "1_1") (pintype "passive"))
      (node (ref "C527") (pin "1") (pinfunction "1_1") (pintype "passive"))
      (node (ref "C528") (pin "1") (pinfunction "1_1") (pintype "passive"))
      (node (ref "U505") (pin "15") (pinfunction "Vdd2_15") (pintype "passive"))
      (node (ref "U505") (pin "9") (pinfunction "Vdd2_9") (pintype "passive"))
      (node (ref "U506") (pin "1") (pinfunction "GND_1") (pintype "power_in"))
      (node (ref "X501") (pin "1") (pinfunction "1_1") (pintype "passive"))
    )
    (net (code "59") (name "Net-(U507-GND)") (class "Default")
      (node (ref "C502") (pin "1") (pinfunction "1_1") (pintype "passive"))
      (node (ref "C529") (pin "1") (pinfunction "1_1") (pintype "passive"))
      (node (ref "C530") (pin "1") (pinfunction "1_1") (pintype "passive"))
      (node (ref "C531") (pin "1") (pinfunction "1_1") (pintype "passive"))
      (node (ref "U500") (pin "15") (pinfunction "Vdd2_15") (pintype "passive"))
      (node (ref "U500") (pin "9") (pinfunction "Vdd2_9") (pintype "passive"))
      (node (ref "U507") (pin "1") (pinfunction "GND_1") (pintype "power_in"))
      (node (ref "X503") (pin "1") (pinfunction "1_1") (pintype "passive"))
    )
    (net (code "60") (name "unconnected-(D511-NC-Pad4)") (class "Default")
      (node (ref "D511") (pin "4") (pinfunction "NC_4") (pintype "passive"))
    )
    (net (code "61") (name "unconnected-(D511-NC-Pad5)") (class "Default")
      (node (ref "D511") (pin "5") (pinfunction "NC_5") (pintype "passive"))
    )
    (net (code "62") (name "unconnected-(JP500-Pad3)") (class "Default")
      (node (ref "JP500") (pin "3") (pinfunction "3_3") (pintype "passive"))
    )
    (net (code "63") (name "unconnected-(JP500-Pad4)") (class "Default")
      (node (ref "JP500") (pin "4") (pinfunction "4_4") (pintype "passive"))
    )
    (net (code "64") (name "unconnected-(JP500-Pad5)") (class "Default")
      (node (ref "JP500") (pin "5") (pinfunction "5_5") (pintype "passive"))
    )
    (net (code "65") (name "unconnected-(JP500-Pad6)") (class "Default")
      (node (ref "JP500") (pin "6") (pinfunction "6_6") (pintype "passive"))
    )
    (net (code "66") (name "unconnected-(JP500-Pad7)") (class "Default")
      (node (ref "JP500") (pin "7") (pinfunction "7_7") (pintype "passive"))
    )
    (net (code "67") (name "unconnected-(JP500-Pad8)") (class "Default")
      (node (ref "JP500") (pin "8") (pinfunction "8_8") (pintype "passive"))
    )
    (net (code "68") (name "unconnected-(L500-Pad9)") (class "Default")
      (node (ref "L500") (pin "9") (pintype "passive"))
    )
    (net (code "69") (name "unconnected-(L500-Pad10)") (class "Default")
      (node (ref "L500") (pin "10") (pinfunction "10_10") (pintype "passive"))
    )
    (net (code "70") (name "unconnected-(U500-PV-Pad7)") (class "Default")
      (node (ref "U500") (pin "7") (pinfunction "PV_7") (pintype "passive"))
    )
    (net (code "71") (name "unconnected-(U501-NC-Pad4)") (class "Default")
      (node (ref "U501") (pin "4") (pinfunction "NC_4") (pintype "passive"))
    )
    (net (code "72") (name "unconnected-(U501-NC-Pad8)") (class "Default")
      (node (ref "U501") (pin "8") (pinfunction "NC_8") (pintype "passive"))
    )
    (net (code "73") (name "unconnected-(U505-PV-Pad7)") (class "Default")
      (node (ref "U505") (pin "7") (pinfunction "PV_7") (pintype "passive"))
    )
    (net (code "74") (name "unconnected-(X507-Pad1)") (class "Default")
      (node (ref "X507") (pin "1") (pinfunction "1_1") (pintype "passive"))
    )
  )
)
